# AmpSSM2019_240119.net
KiCad netlist of a schematic drawn in EAGLE
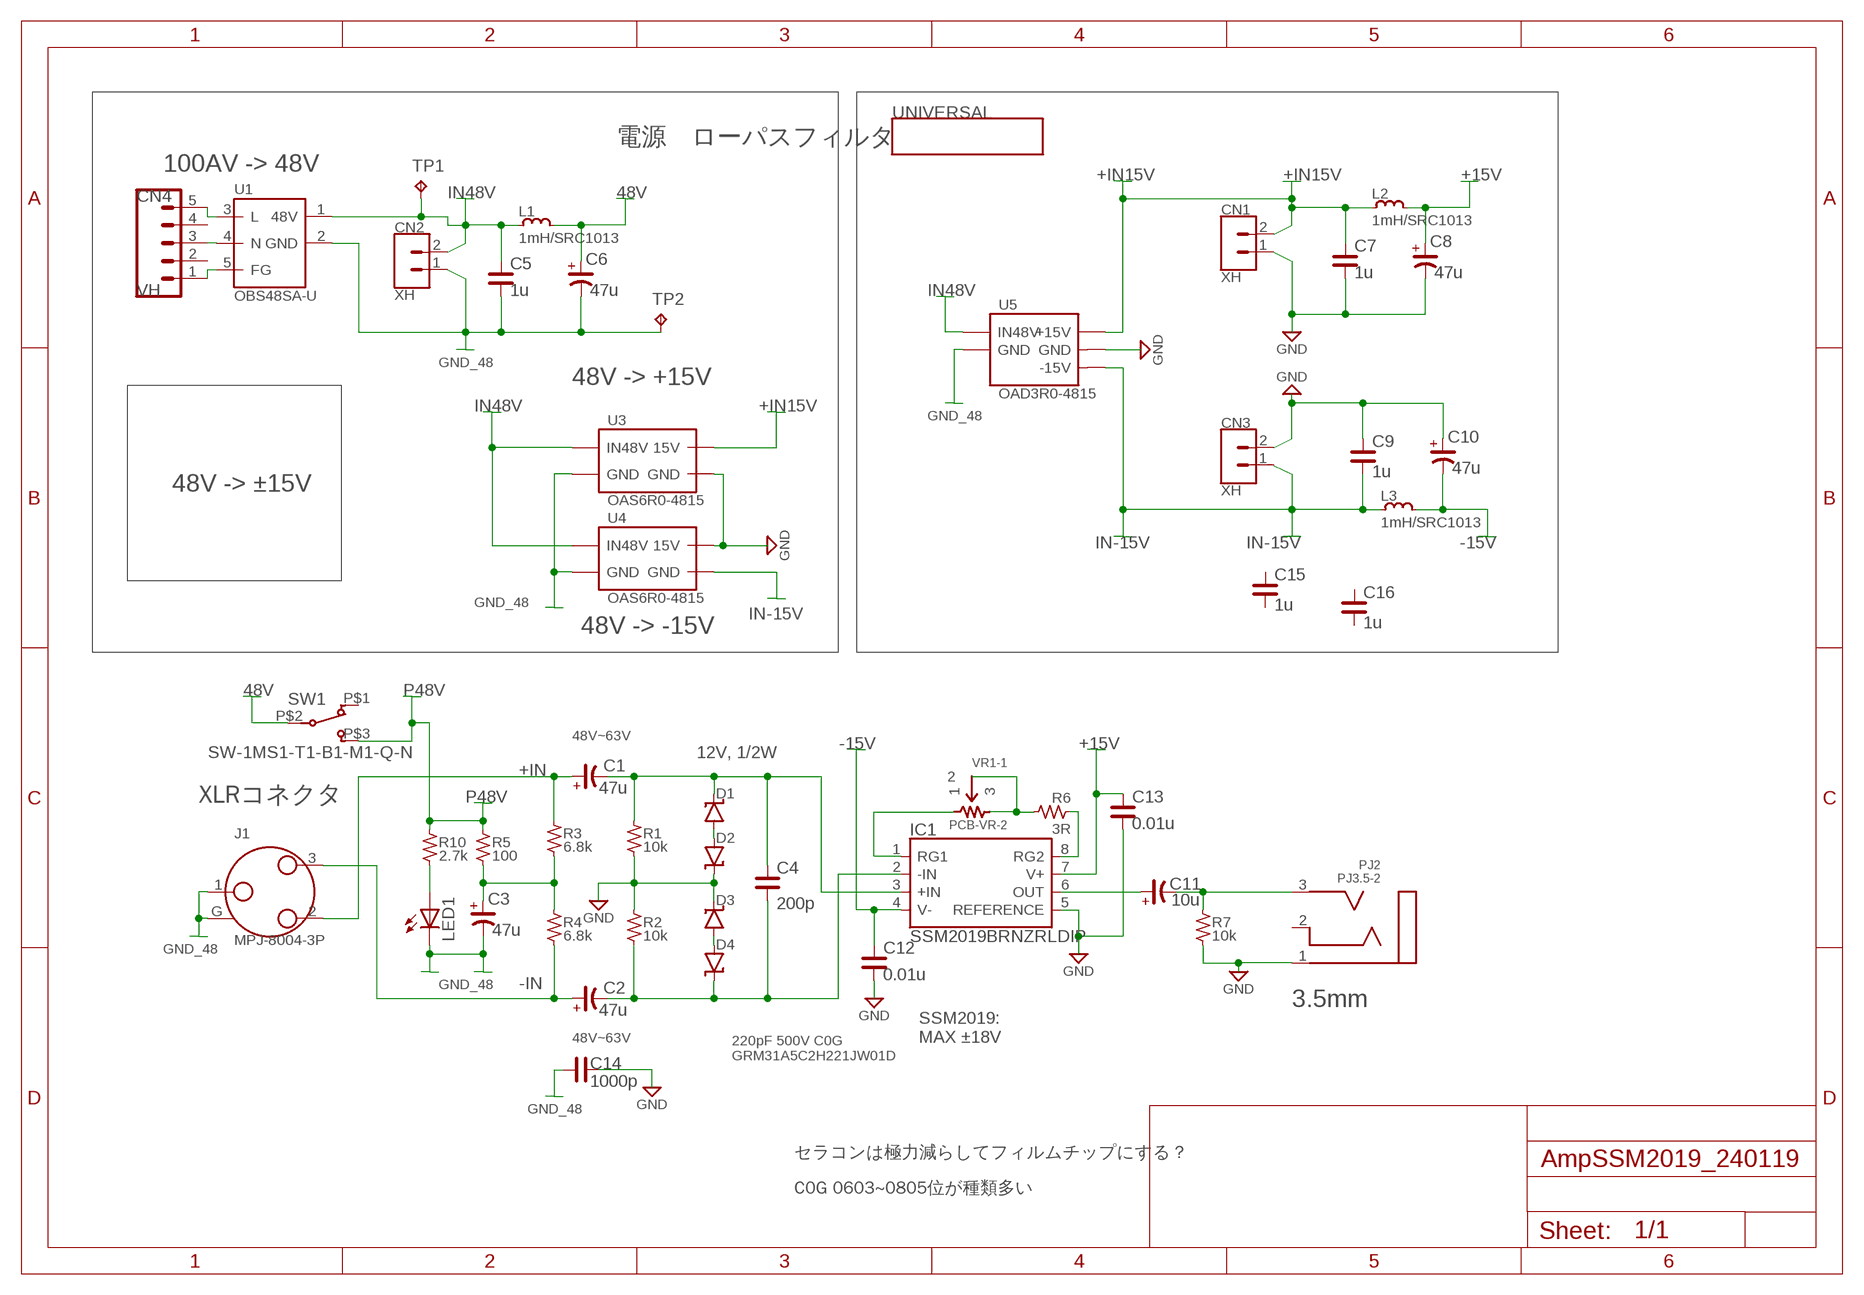
[diagram p0: schematic, sheet 1]

(export (version "E")
  (design (tool "Eeschema 10.0.6"))
  (components
    (comp (ref "C1")
      (value "47u")
      (footprint "eagle-import:CE-025X065")
      (libsource (lib "eagle-import") (part "CP_C025X065"))
    )
    (comp (ref "C2")
      (value "47u")
      (footprint "eagle-import:CE-025X065")
      (libsource (lib "eagle-import") (part "CP_C025X065"))
    )
    (comp (ref "C3")
      (value "47u")
      (footprint "eagle-import:CE-025X065")
      (libsource (lib "eagle-import") (part "CP_C025X065"))
    )
    (comp (ref "C4")
      (value "200p")
      (footprint "eagle-import:C1206")
      (libsource (lib "eagle-import") (part "C_1206"))
    )
    (comp (ref "C5")
      (value "1u")
      (footprint "eagle-import:C1206")
      (libsource (lib "eagle-import") (part "C_1206"))
    )
    (comp (ref "C6")
      (value "47u")
      (footprint "eagle-import:CE-025X065")
      (libsource (lib "eagle-import") (part "CP_C025X065"))
    )
    (comp (ref "C7")
      (value "1u")
      (footprint "eagle-import:C1206")
      (libsource (lib "eagle-import") (part "C_1206"))
    )
    (comp (ref "C8")
      (value "47u")
      (footprint "eagle-import:CE-025X065")
      (libsource (lib "eagle-import") (part "CP_C025X065"))
    )
    (comp (ref "C9")
      (value "1u")
      (footprint "eagle-import:C1206")
      (libsource (lib "eagle-import") (part "C_1206"))
    )
    (comp (ref "C10")
      (value "47u")
      (footprint "eagle-import:CE-025X065")
      (libsource (lib "eagle-import") (part "CP_C025X065"))
    )
    (comp (ref "C11")
      (value "10u")
      (footprint "eagle-import:CE-025X065")
      (libsource (lib "eagle-import") (part "CP_C025X065"))
    )
    (comp (ref "C12")
      (value "0.01u")
      (footprint "eagle-import:C0603")
      (libsource (lib "eagle-import") (part "C_0603"))
    )
    (comp (ref "C13")
      (value "0.01u")
      (footprint "eagle-import:C0603")
      (libsource (lib "eagle-import") (part "C_0603"))
    )
    (comp (ref "C14")
      (value "1000p")
      (footprint "eagle-import:C1206")
      (libsource (lib "eagle-import") (part "C_1206"))
    )
    (comp (ref "C15")
      (value "1u")
      (footprint "eagle-import:C050-065X075")
      (libsource (lib "eagle-import") (part "C_F1"))
    )
    (comp (ref "C16")
      (value "1u")
      (footprint "eagle-import:C050-045X075")
      (libsource (lib "eagle-import") (part "C_F0.1"))
    )
    (comp (ref "CN1")
      (value "XH")
      (footprint "eagle-import:B2B-XH-A")
      (libsource (lib "eagle-import") (part "CN-B2B-XH-A"))
    )
    (comp (ref "CN2")
      (value "XH")
      (footprint "eagle-import:B2B-XH-A")
      (libsource (lib "eagle-import") (part "CN-B2B-XH-A"))
    )
    (comp (ref "CN3")
      (value "XH")
      (footprint "eagle-import:B2B-XH-A")
      (libsource (lib "eagle-import") (part "CN-B2B-XH-A"))
    )
    (comp (ref "CN4")
      (value "VH")
      (footprint "eagle-import:VH5")
      (libsource (lib "eagle-import") (part "M05VH"))
    )
    (comp (ref "D1")
      (value "ZD323")
      (footprint "eagle-import:SOD-323")
      (libsource (lib "eagle-import") (part "ZD323"))
    )
    (comp (ref "D2")
      (value "ZD323")
      (footprint "eagle-import:SOD-323")
      (libsource (lib "eagle-import") (part "ZD323"))
    )
    (comp (ref "D3")
      (value "ZD323")
      (footprint "eagle-import:SOD-323")
      (libsource (lib "eagle-import") (part "ZD323"))
    )
    (comp (ref "D4")
      (value "ZD323")
      (footprint "eagle-import:SOD-323")
      (libsource (lib "eagle-import") (part "ZD323"))
    )
    (comp (ref "IC1")
      (value "SSM2019BRNZRLDIP")
      (footprint "eagle-import:DIL08")
      (libsource (lib "eagle-import") (part "SSM2019BRNZRLDIP"))
    )
    (comp (ref "J1")
      (value "MPJ-8004-3P")
      (footprint "eagle-import:MPJ-8004-3P")
      (libsource (lib "eagle-import") (part "MPJ-8004-3P"))
    )
    (comp (ref "L1")
      (value "1mH/SRC1013")
      (footprint "eagle-import:L13X15")
      (libsource (lib "eagle-import") (part "L_13X15"))
    )
    (comp (ref "L2")
      (value "1mH/SRC1013")
      (footprint "eagle-import:L13X15")
      (libsource (lib "eagle-import") (part "L_13X15"))
    )
    (comp (ref "L3")
      (value "1mH/SRC1013")
      (footprint "eagle-import:L13X15")
      (libsource (lib "eagle-import") (part "L_13X15"))
    )
    (comp (ref "LED1")
      (value "LED3MM")
      (footprint "eagle-import:LED3MM")
      (libsource (lib "eagle-import") (part "LED3MM"))
    )
    (comp (ref "PJ2")
      (value "PJ3.5-2")
      (footprint "eagle-import:PJ3.5-2")
      (libsource (lib "eagle-import") (part "PJ3.5-2"))
    )
    (comp (ref "R1")
      (value "10k")
      (footprint "eagle-import:R0603")
      (libsource (lib "eagle-import") (part "R_0603"))
    )
    (comp (ref "R2")
      (value "10k")
      (footprint "eagle-import:R0603")
      (libsource (lib "eagle-import") (part "R_0603"))
    )
    (comp (ref "R3")
      (value "6.8k")
      (footprint "eagle-import:R0603")
      (libsource (lib "eagle-import") (part "R_0603"))
    )
    (comp (ref "R4")
      (value "6.8k")
      (footprint "eagle-import:R0603")
      (libsource (lib "eagle-import") (part "R_0603"))
    )
    (comp (ref "R5")
      (value "100")
      (footprint "eagle-import:R0603")
      (libsource (lib "eagle-import") (part "R_0603"))
    )
    (comp (ref "R6")
      (value "3R")
      (footprint "eagle-import:R0603")
      (libsource (lib "eagle-import") (part "R_0603"))
    )
    (comp (ref "R7")
      (value "10k")
      (footprint "eagle-import:R0603")
      (libsource (lib "eagle-import") (part "R_0603"))
    )
    (comp (ref "R10")
      (value "2.7k")
      (footprint "eagle-import:R0603")
      (libsource (lib "eagle-import") (part "R_0603"))
    )
    (comp (ref "SW1")
      (value "SW-1MS1-T1-B1-M1-Q-N")
      (footprint "eagle-import:1MS1-T1-B1-M1-Q-N")
      (libsource (lib "eagle-import") (part "SW-1MS1-T1-B1-M1-Q-N"))
    )
    (comp (ref "TP1")
      (value "TPPAD1-13")
      (footprint "eagle-import:P1-13")
      (libsource (lib "eagle-import") (part "TPPAD1-13"))
    )
    (comp (ref "TP2")
      (value "TPPAD1-13")
      (footprint "eagle-import:P1-13")
      (libsource (lib "eagle-import") (part "TPPAD1-13"))
    )
    (comp (ref "U1")
      (value "OBS48SA-U")
      (footprint "eagle-import:OBS48SA-U")
      (libsource (lib "eagle-import") (part "OBS48SA-U"))
    )
    (comp (ref "U2")
      (value "UNIVERSAL10X10")
      (footprint "eagle-import:UNIVERSAL10X10")
      (libsource (lib "eagle-import") (part "UNIVERSAL10X10"))
    )
    (comp (ref "U3")
      (value "OAS6R0-4815")
      (footprint "eagle-import:OAS6R0-4815")
      (libsource (lib "eagle-import") (part "OAS6R0-4815"))
    )
    (comp (ref "U4")
      (value "OAS6R0-4815")
      (footprint "eagle-import:OAS6R0-4815")
      (libsource (lib "eagle-import") (part "OAS6R0-4815"))
    )
    (comp (ref "U5")
      (value "OAD3R0-4815")
      (footprint "eagle-import:OAD3R0-4815")
      (libsource (lib "eagle-import") (part "OAD3R0-4815"))
    )
    (comp (ref "VR1")
      (value "PCB-VR-2")
      (footprint "eagle-import:PCB-VR-2")
      (libsource (lib "eagle-import") (part "PCB-VR-2"))
    )
  )
  (nets
    (net (code "1") (name "/+15V") (class "Default")
      (node (ref "C13") (pin "2") (pinfunction "2_2") (pintype "passive"))
      (node (ref "C8") (pin "+") (pinfunction "+_+") (pintype "passive"))
      (node (ref "IC1") (pin "7") (pinfunction "V+_7") (pintype "bidirectional"))
      (node (ref "L2") (pin "2") (pinfunction "2_2") (pintype "passive"))
    )
    (net (code "2") (name "/+IN") (class "Default")
      (node (ref "C1") (pin "+") (pinfunction "+_+") (pintype "passive"))
      (node (ref "J1") (pin "2") (pinfunction "2_2") (pintype "bidirectional"))
      (node (ref "R3") (pin "2") (pinfunction "2_2") (pintype "passive"))
    )
    (net (code "3") (name "/+IN15V") (class "Default")
      (node (ref "C7") (pin "2") (pinfunction "2_2") (pintype "passive"))
      (node (ref "CN1") (pin "2") (pinfunction "2_2") (pintype "passive"))
      (node (ref "L2") (pin "1") (pinfunction "1_1") (pintype "passive"))
      (node (ref "U3") (pin "V_OUT") (pinfunction "15V_V_OUT") (pintype "bidirectional"))
      (node (ref "U5") (pin "V+_OUT") (pinfunction "+15V_V+_OUT") (pintype "bidirectional"))
    )
    (net (code "4") (name "/-15V") (class "Default")
      (node (ref "C10") (pin "-") (pinfunction "-_-") (pintype "passive"))
      (node (ref "C12") (pin "2") (pinfunction "2_2") (pintype "passive"))
      (node (ref "IC1") (pin "4") (pinfunction "V-_4") (pintype "bidirectional"))
      (node (ref "L3") (pin "2") (pinfunction "2_2") (pintype "passive"))
    )
    (net (code "5") (name "/-IN") (class "Default")
      (node (ref "C2") (pin "+") (pinfunction "+_+") (pintype "passive"))
      (node (ref "J1") (pin "3") (pinfunction "3_3") (pintype "bidirectional"))
      (node (ref "R4") (pin "1") (pinfunction "1_1") (pintype "passive"))
    )
    (net (code "6") (name "/48V") (class "Default")
      (node (ref "C6") (pin "+") (pinfunction "+_+") (pintype "passive"))
      (node (ref "L1") (pin "2") (pinfunction "2_2") (pintype "passive"))
      (node (ref "SW1") (pin "P$2") (pinfunction "P_P$2") (pintype "passive"))
    )
    (net (code "7") (name "/GND_48") (class "Default")
      (node (ref "C14") (pin "2") (pinfunction "2_2") (pintype "passive"))
      (node (ref "C3") (pin "-") (pinfunction "-_-") (pintype "passive"))
      (node (ref "C5") (pin "1") (pinfunction "1_1") (pintype "passive"))
      (node (ref "C6") (pin "-") (pinfunction "-_-") (pintype "passive"))
      (node (ref "CN2") (pin "1") (pinfunction "1_1") (pintype "passive"))
      (node (ref "J1") (pin "1") (pinfunction "1_1") (pintype "bidirectional"))
      (node (ref "J1") (pin "G") (pinfunction "G_G") (pintype "bidirectional"))
      (node (ref "LED1") (pin "K") (pinfunction "C_K") (pintype "passive"))
      (node (ref "TP2") (pin "TP") (pinfunction "TP_TP") (pintype "input"))
      (node (ref "U1") (pin "2") (pinfunction "GND_2") (pintype "bidirectional"))
      (node (ref "U3") (pin "G_IN") (pinfunction "GND_G_IN") (pintype "bidirectional"))
      (node (ref "U4") (pin "G_IN") (pinfunction "GND_G_IN") (pintype "bidirectional"))
      (node (ref "U5") (pin "G_IN") (pinfunction "GND_G_IN") (pintype "bidirectional"))
    )
    (net (code "8") (name "/IN-15V") (class "Default")
      (node (ref "C9") (pin "2") (pinfunction "2_2") (pintype "passive"))
      (node (ref "CN3") (pin "1") (pinfunction "1_1") (pintype "passive"))
      (node (ref "L3") (pin "1") (pinfunction "1_1") (pintype "passive"))
      (node (ref "U4") (pin "G_OUT") (pinfunction "GND_G_OUT") (pintype "bidirectional"))
      (node (ref "U5") (pin "V-_OUT") (pinfunction "-15V_V-_OUT") (pintype "bidirectional"))
    )
    (net (code "9") (name "/IN48V") (class "Default")
      (node (ref "C5") (pin "2") (pinfunction "2_2") (pintype "passive"))
      (node (ref "CN2") (pin "2") (pinfunction "2_2") (pintype "passive"))
      (node (ref "L1") (pin "1") (pinfunction "1_1") (pintype "passive"))
      (node (ref "TP1") (pin "TP") (pinfunction "TP_TP") (pintype "input"))
      (node (ref "U1") (pin "1") (pinfunction "48V_1") (pintype "bidirectional"))
      (node (ref "U3") (pin "VIN") (pinfunction "IN48V_VIN") (pintype "bidirectional"))
      (node (ref "U4") (pin "VIN") (pinfunction "IN48V_VIN") (pintype "bidirectional"))
      (node (ref "U5") (pin "VIN") (pinfunction "IN48V_VIN") (pintype "bidirectional"))
    )
    (net (code "10") (name "/P48V") (class "Default")
      (node (ref "R10") (pin "2") (pinfunction "2_2") (pintype "passive"))
      (node (ref "R5") (pin "2") (pinfunction "2_2") (pintype "passive"))
      (node (ref "SW1") (pin "P$3") (pinfunction "S_P$3") (pintype "passive"))
    )
    (net (code "11") (name "G") (class "Default")
      (node (ref "C10") (pin "+") (pinfunction "+_+") (pintype "passive"))
      (node (ref "C12") (pin "1") (pinfunction "1_1") (pintype "passive"))
      (node (ref "C13") (pin "1") (pinfunction "1_1") (pintype "passive"))
      (node (ref "C14") (pin "1") (pinfunction "1_1") (pintype "passive"))
      (node (ref "C7") (pin "1") (pinfunction "1_1") (pintype "passive"))
      (node (ref "C8") (pin "-") (pinfunction "-_-") (pintype "passive"))
      (node (ref "C9") (pin "1") (pinfunction "1_1") (pintype "passive"))
      (node (ref "CN1") (pin "1") (pinfunction "1_1") (pintype "passive"))
      (node (ref "CN3") (pin "2") (pinfunction "2_2") (pintype "passive"))
      (node (ref "D2") (pin "K") (pinfunction "C_K") (pintype "passive"))
      (node (ref "D3") (pin "K") (pinfunction "C_K") (pintype "passive"))
      (node (ref "IC1") (pin "5") (pinfunction "REFERENCE_5") (pintype "bidirectional"))
      (node (ref "PJ2") (pin "1") (pinfunction "S_1") (pintype "passive"))
      (node (ref "R1") (pin "1") (pinfunction "1_1") (pintype "passive"))
      (node (ref "R2") (pin "2") (pinfunction "2_2") (pintype "passive"))
      (node (ref "R7") (pin "1") (pinfunction "1_1") (pintype "passive"))
      (node (ref "U3") (pin "G_OUT") (pinfunction "GND_G_OUT") (pintype "bidirectional"))
      (node (ref "U4") (pin "V_OUT") (pinfunction "15V_V_OUT") (pintype "bidirectional"))
      (node (ref "U5") (pin "G_OUT") (pinfunction "GND_G_OUT") (pintype "bidirectional"))
    )
    (net (code "12") (name "Net-(C3-Pad+)") (class "Default")
      (node (ref "C3") (pin "+") (pinfunction "+_+") (pintype "passive"))
      (node (ref "R3") (pin "1") (pinfunction "1_1") (pintype "passive"))
      (node (ref "R4") (pin "2") (pinfunction "2_2") (pintype "passive"))
      (node (ref "R5") (pin "1") (pinfunction "1_1") (pintype "passive"))
    )
    (net (code "13") (name "Net-(D1-C)") (class "Default")
      (node (ref "C1") (pin "-") (pinfunction "-_-") (pintype "passive"))
      (node (ref "C4") (pin "2") (pinfunction "2_2") (pintype "passive"))
      (node (ref "D1") (pin "K") (pinfunction "C_K") (pintype "passive"))
      (node (ref "IC1") (pin "3") (pinfunction "+IN_3") (pintype "bidirectional"))
      (node (ref "R1") (pin "2") (pinfunction "2_2") (pintype "passive"))
    )
    (net (code "14") (name "Net-(D1-PadA)") (class "Default")
      (node (ref "D1") (pin "A") (pinfunction "A_A") (pintype "passive"))
      (node (ref "D2") (pin "A") (pinfunction "A_A") (pintype "passive"))
    )
    (net (code "15") (name "Net-(D3-PadA)") (class "Default")
      (node (ref "D3") (pin "A") (pinfunction "A_A") (pintype "passive"))
      (node (ref "D4") (pin "A") (pinfunction "A_A") (pintype "passive"))
    )
    (net (code "16") (name "Net-(D4-C)") (class "Default")
      (node (ref "C2") (pin "-") (pinfunction "-_-") (pintype "passive"))
      (node (ref "C4") (pin "1") (pinfunction "1_1") (pintype "passive"))
      (node (ref "D4") (pin "K") (pinfunction "C_K") (pintype "passive"))
      (node (ref "IC1") (pin "2") (pinfunction "-IN_2") (pintype "bidirectional"))
      (node (ref "R2") (pin "1") (pinfunction "1_1") (pintype "passive"))
    )
    (net (code "17") (name "Net-(IC1-OUT)") (class "Default")
      (node (ref "C11") (pin "+") (pinfunction "+_+") (pintype "passive"))
      (node (ref "IC1") (pin "6") (pinfunction "OUT_6") (pintype "bidirectional"))
    )
    (net (code "18") (name "Net-(IC1-RG1)") (class "Default")
      (node (ref "IC1") (pin "1") (pinfunction "RG1_1") (pintype "bidirectional"))
      (node (ref "VR1") (pin "3") (pinfunction "1_3") (pintype "passive"))
    )
    (net (code "19") (name "Net-(IC1-RG2)") (class "Default")
      (node (ref "IC1") (pin "8") (pinfunction "RG2_8") (pintype "bidirectional"))
      (node (ref "R6") (pin "1") (pinfunction "1_1") (pintype "passive"))
    )
    (net (code "20") (name "Net-(LED1-PadA)") (class "Default")
      (node (ref "LED1") (pin "A") (pinfunction "A_A") (pintype "passive"))
      (node (ref "R10") (pin "1") (pinfunction "1_1") (pintype "passive"))
    )
    (net (code "21") (name "Net-(PJ2-TIP)") (class "Default")
      (node (ref "C11") (pin "-") (pinfunction "-_-") (pintype "passive"))
      (node (ref "PJ2") (pin "3") (pinfunction "TIP_3") (pintype "passive"))
      (node (ref "R7") (pin "2") (pinfunction "2_2") (pintype "passive"))
    )
    (net (code "22") (name "Net-(U1-FG)") (class "Default")
      (node (ref "CN4") (pin "1") (pinfunction "1_1") (pintype "passive"))
      (node (ref "U1") (pin "5") (pinfunction "FG_5") (pintype "bidirectional"))
    )
    (net (code "23") (name "Net-(U1-L)") (class "Default")
      (node (ref "CN4") (pin "5") (pinfunction "5_5") (pintype "passive"))
      (node (ref "U1") (pin "3") (pinfunction "L_3") (pintype "bidirectional"))
    )
    (net (code "24") (name "Net-(U1-N)") (class "Default")
      (node (ref "CN4") (pin "3") (pinfunction "3_3") (pintype "passive"))
      (node (ref "U1") (pin "4") (pinfunction "N_4") (pintype "bidirectional"))
    )
    (net (code "25") (name "Net-(VR1A-3)") (class "Default")
      (node (ref "R6") (pin "2") (pinfunction "2_2") (pintype "passive"))
      (node (ref "VR1") (pin "1") (pinfunction "3_1") (pintype "passive"))
      (node (ref "VR1") (pin "2") (pinfunction "2_2") (pintype "passive"))
    )
    (net (code "26") (name "unconnected-(C15-Pad1)") (class "Default")
      (node (ref "C15") (pin "1") (pinfunction "1_1") (pintype "passive"))
    )
    (net (code "27") (name "unconnected-(C15-Pad2)") (class "Default")
      (node (ref "C15") (pin "2") (pinfunction "2_2") (pintype "passive"))
    )
    (net (code "28") (name "unconnected-(C16-Pad1)") (class "Default")
      (node (ref "C16") (pin "1") (pinfunction "1_1") (pintype "passive"))
    )
    (net (code "29") (name "unconnected-(C16-Pad2)") (class "Default")
      (node (ref "C16") (pin "2") (pinfunction "2_2") (pintype "passive"))
    )
    (net (code "30") (name "unconnected-(CN4-Pad2)") (class "Default")
      (node (ref "CN4") (pin "2") (pinfunction "2_2") (pintype "passive"))
    )
    (net (code "31") (name "unconnected-(CN4-Pad4)") (class "Default")
      (node (ref "CN4") (pin "4") (pinfunction "4_4") (pintype "passive"))
    )
    (net (code "32") (name "unconnected-(PJ2-RING-Pad2)") (class "Default")
      (node (ref "PJ2") (pin "2") (pinfunction "RING_2") (pintype "passive"))
    )
    (net (code "33") (name "unconnected-(SW1-O-PadP$1)") (class "Default")
      (node (ref "SW1") (pin "P$1") (pinfunction "O_P$1") (pintype "passive"))
    )
  )
)
